# Peripherals.net
KiCad netlist of a schematic drawn in Altium Designer
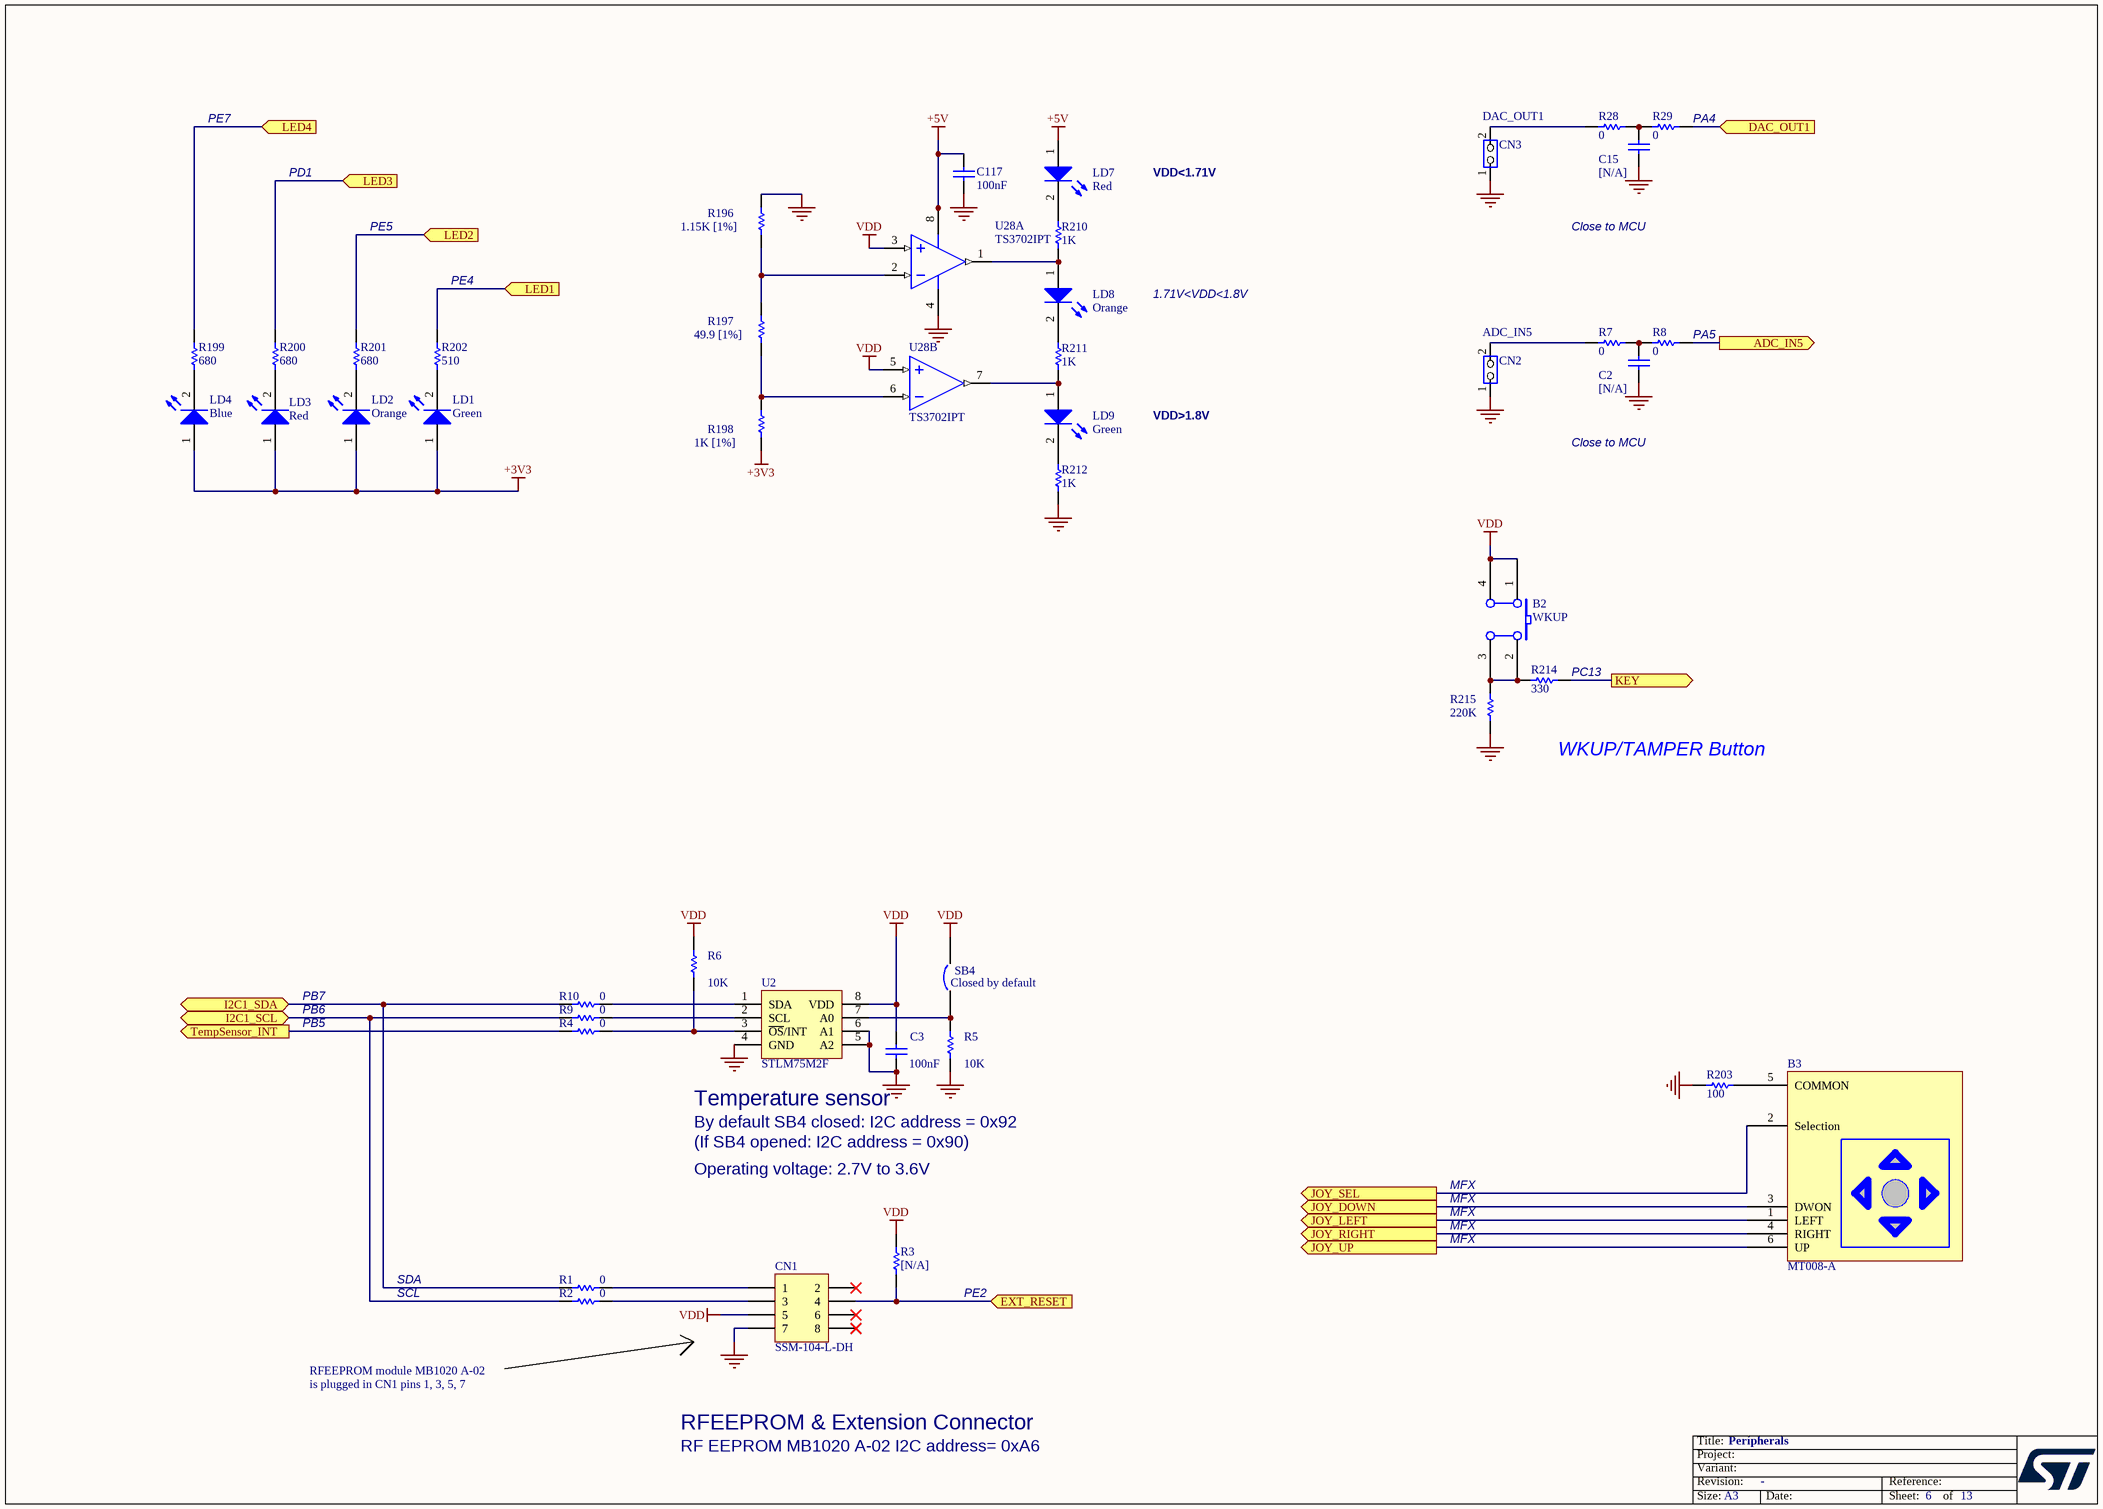
[diagram p0: Peripherals.SchDoc]

(export (version "E")
  (design (tool "Eeschema 10.0.6"))
  (components
    (comp (ref "B2")
      (value "WKUP")
      (footprint "PB10")
      (description "SE PUSHBUTTON")
      (libsource (lib "Documents") (part "SW PUSHBUTTON"))
    )
    (comp (ref "B3")
      (value "MT008-A")
      (footprint "MT-008A")
      (description "Joystick")
      (libsource (lib "MB513") (part "MT-008A"))
    )
    (comp (ref "C2")
      (value "[N/A]")
      (footprint "0603C")
      (description "Capacitor")
      (fields (field (name "PUBLISHER") "Altium Limited"))
      (libsource (lib "Miscellaneous Devices") (part "cap"))
    )
    (comp (ref "C3")
      (value "100nF")
      (footprint "0402C")
      (description "Capacitor")
      (fields (field (name "PUBLISHER") "Altium Limited"))
      (libsource (lib "Miscellaneous Devices") (part "cap"))
    )
    (comp (ref "C15")
      (value "[N/A]")
      (footprint "0603C")
      (description "Capacitor")
      (fields (field (name "PUBLISHER") "Altium Limited"))
      (libsource (lib "Miscellaneous Devices") (part "cap"))
    )
    (comp (ref "C117")
      (value "100nF")
      (footprint "0402C")
      (description "Capacitor")
      (fields (field (name "PUBLISHER") "Altium Limited"))
      (libsource (lib "Miscellaneous Devices") (part "CAP"))
    )
    (comp (ref "CN1")
      (value "SSM-104-L-DH")
      (footprint "SSM-104-L-DH")
      (description "Header, 5-Pin, Dual row")
      (fields (field (name "PUBLISHER") "Altium Limited"))
      (libsource (lib "mb1045") (part "SSM-104-L-DH"))
    )
    (comp (ref "CN2")
      (value "Header 2X1")
      (footprint "SIP2")
      (fields (field (name "SILKSCREEN") "ADC_IN5"))
      (libsource (lib "*") (part "JP2"))
    )
    (comp (ref "CN3")
      (value "Header 2X1")
      (footprint "SIP2")
      (fields (field (name "SILKSCREEN") "DAC_OUT1"))
      (libsource (lib "*") (part "JP2"))
    )
    (comp (ref "LD1")
      (value "Green")
      (footprint "0603D")
      (description "Typical RED, GREEN, YELLOW, AMBER GaAs LED")
      (fields (field (name "PUBLISHER") "Altium Limited"))
      (libsource (lib "Miscellaneous Devices") (part "LED2"))
    )
    (comp (ref "LD2")
      (value "Orange")
      (footprint "0603D")
      (description "Typical RED, GREEN, YELLOW, AMBER GaAs LED")
      (fields (field (name "PUBLISHER") "Altium Limited"))
      (libsource (lib "Miscellaneous Devices") (part "LED2"))
    )
    (comp (ref "LD3")
      (value "Red")
      (footprint "0603D")
      (description "Typical RED, GREEN, YELLOW, AMBER GaAs LED")
      (fields (field (name "PUBLISHER") "Altium Limited"))
      (libsource (lib "Miscellaneous Devices") (part "LED2"))
    )
    (comp (ref "LD4")
      (value "Blue")
      (footprint "0603D")
      (description "Typical RED, GREEN, YELLOW, AMBER GaAs LED")
      (fields (field (name "PUBLISHER") "Altium Limited"))
      (libsource (lib "Miscellaneous Devices") (part "LED2"))
    )
    (comp (ref "LD7")
      (value "Red")
      (footprint "0603D")
      (description "Typical RED, GREEN, YELLOW, AMBER GaAs LED")
      (fields (field (name "PUBLISHER") "Altium Limited"))
      (libsource (lib "Miscellaneous Devices") (part "LED2"))
    )
    (comp (ref "LD8")
      (value "Orange")
      (footprint "0603D")
      (description "Typical RED, GREEN, YELLOW, AMBER GaAs LED")
      (fields (field (name "PUBLISHER") "Altium Limited"))
      (libsource (lib "Miscellaneous Devices") (part "LED2"))
    )
    (comp (ref "LD9")
      (value "Green")
      (footprint "0603D")
      (description "Typical RED, GREEN, YELLOW, AMBER GaAs LED")
      (fields (field (name "PUBLISHER") "Altium Limited"))
      (libsource (lib "Miscellaneous Devices") (part "LED2"))
    )
    (comp (ref "R1")
      (value "0")
      (footprint "0603R")
      (description "Resistor")
      (fields (field (name "PUBLISHER") "Altium Limited"))
      (libsource (lib "Miscellaneous Devices") (part "Res1"))
    )
    (comp (ref "R2")
      (value "0")
      (footprint "0603R")
      (description "Resistor")
      (fields (field (name "PUBLISHER") "Altium Limited"))
      (libsource (lib "Miscellaneous Devices") (part "Res1"))
    )
    (comp (ref "R3")
      (value "[N/A]")
      (footprint "0603R")
      (description "Resistor")
      (fields (field (name "PUBLISHER") "Altium Limited"))
      (libsource (lib "Miscellaneous Devices") (part "Res1"))
    )
    (comp (ref "R4")
      (value "0")
      (footprint "0603R")
      (description "Resistor")
      (fields (field (name "PUBLISHER") "Altium Limited"))
      (libsource (lib "Miscellaneous Devices") (part "Res1"))
    )
    (comp (ref "R5")
      (value "10K")
      (footprint "0402R")
      (description "Resistor")
      (fields (field (name "PUBLISHER") "Altium Limited"))
      (libsource (lib "Miscellaneous Devices") (part "res1"))
    )
    (comp (ref "R6")
      (value "10K")
      (footprint "0402R")
      (description "Resistor")
      (fields (field (name "PUBLISHER") "Altium Limited"))
      (libsource (lib "Miscellaneous Devices") (part "res1"))
    )
    (comp (ref "R7")
      (value "0")
      (footprint "0603R")
      (description "Resistor")
      (fields (field (name "PUBLISHER") "Altium Limited"))
      (libsource (lib "Miscellaneous Devices") (part "Res1"))
    )
    (comp (ref "R8")
      (value "0")
      (footprint "0603R")
      (description "Resistor")
      (fields (field (name "PUBLISHER") "Altium Limited"))
      (libsource (lib "Miscellaneous Devices") (part "Res1"))
    )
    (comp (ref "R9")
      (value "0")
      (footprint "0603R")
      (description "Resistor")
      (fields (field (name "PUBLISHER") "Altium Limited"))
      (libsource (lib "Miscellaneous Devices") (part "Res1"))
    )
    (comp (ref "R10")
      (value "0")
      (footprint "0603R")
      (description "Resistor")
      (fields (field (name "PUBLISHER") "Altium Limited"))
      (libsource (lib "Miscellaneous Devices") (part "Res1"))
    )
    (comp (ref "R28")
      (value "0")
      (footprint "0603R")
      (description "Resistor")
      (fields (field (name "PUBLISHER") "Altium Limited"))
      (libsource (lib "Miscellaneous Devices") (part "Res1"))
    )
    (comp (ref "R29")
      (value "0")
      (footprint "0603R")
      (description "Resistor")
      (fields (field (name "PUBLISHER") "Altium Limited"))
      (libsource (lib "Miscellaneous Devices") (part "Res1"))
    )
    (comp (ref "R196")
      (value "1.15K [1%]")
      (footprint "0603R")
      (description "Resistor")
      (fields (field (name "PUBLISHER") "Altium Limited"))
      (libsource (lib "Miscellaneous Devices") (part "Res1"))
    )
    (comp (ref "R197")
      (value "49.9 [1%]")
      (footprint "0603R")
      (description "Resistor")
      (fields (field (name "PUBLISHER") "Altium Limited"))
      (libsource (lib "Miscellaneous Devices") (part "Res1"))
    )
    (comp (ref "R198")
      (value "1K [1%]")
      (footprint "0603R")
      (description "Resistor")
      (fields (field (name "PUBLISHER") "Altium Limited"))
      (libsource (lib "Miscellaneous Devices") (part "Res1"))
    )
    (comp (ref "R199")
      (value "680")
      (footprint "0402R")
      (description "Resistor")
      (fields (field (name "PUBLISHER") "Altium Limited"))
      (libsource (lib "Miscellaneous Devices") (part "Res1"))
    )
    (comp (ref "R200")
      (value "680")
      (footprint "0402R")
      (description "Resistor")
      (fields (field (name "PUBLISHER") "Altium Limited"))
      (libsource (lib "Miscellaneous Devices") (part "Res1"))
    )
    (comp (ref "R201")
      (value "680")
      (footprint "0402R")
      (description "Resistor")
      (fields (field (name "PUBLISHER") "Altium Limited"))
      (libsource (lib "Miscellaneous Devices") (part "Res1"))
    )
    (comp (ref "R202")
      (value "510")
      (footprint "0402R")
      (description "Resistor")
      (fields (field (name "PUBLISHER") "Altium Limited"))
      (libsource (lib "Miscellaneous Devices") (part "Res1"))
    )
    (comp (ref "R203")
      (value "100")
      (footprint "0402R")
      (description "Resistor")
      (fields (field (name "PUBLISHER") "Altium Limited"))
      (libsource (lib "Miscellaneous Devices") (part "Res1"))
    )
    (comp (ref "R210")
      (value "1K")
      (footprint "0402R")
      (description "Resistor")
      (fields (field (name "PUBLISHER") "Altium Limited"))
      (libsource (lib "Miscellaneous Devices") (part "Res1"))
    )
    (comp (ref "R211")
      (value "1K")
      (footprint "0402R")
      (description "Resistor")
      (fields (field (name "PUBLISHER") "Altium Limited"))
      (libsource (lib "Miscellaneous Devices") (part "Res1"))
    )
    (comp (ref "R212")
      (value "1K")
      (footprint "0402R")
      (description "Resistor")
      (fields (field (name "PUBLISHER") "Altium Limited"))
      (libsource (lib "Miscellaneous Devices") (part "Res1"))
    )
    (comp (ref "R214")
      (value "330")
      (footprint "0603R")
      (description "Resistor")
      (fields (field (name "PUBLISHER") "Altium Limited"))
      (libsource (lib "Miscellaneous Devices") (part "Res1"))
    )
    (comp (ref "R215")
      (value "220K")
      (footprint "0402R")
      (description "Resistor")
      (fields (field (name "PUBLISHER") "Altium Limited"))
      (libsource (lib "Miscellaneous Devices") (part "res1"))
    )
    (comp (ref "SB4")
      (value "Closed by default")
      (footprint "SB_0603")
      (description "Circuit Breaker")
      (fields (field (name "PUBLISHER") "Altium Limited"))
      (libsource (lib "Miscellaneous Devices") (part "Circuit Breaker"))
    )
    (comp (ref "U2")
      (value "STLM75M2F")
      (footprint "SOIC8_1R27_4R9X6")
      (libsource (lib "MB525") (part "STLM75DW2F"))
    )
    (comp (ref "U28")
      (value "TS3702IPT")
      (footprint "TSSOP8_0R65_3X6R4")
      (libsource (lib "MB819") (part "LM393PT"))
    )
  )
  (nets
    (net (code "1") (name "+3V3") (class "Default")
      (node (ref "LD1") (pin "1") (pinfunction "A_1") (pintype "passive"))
      (node (ref "LD2") (pin "1") (pinfunction "A_1") (pintype "passive"))
      (node (ref "LD3") (pin "1") (pinfunction "A_1") (pintype "passive"))
      (node (ref "LD4") (pin "1") (pinfunction "A_1") (pintype "passive"))
      (node (ref "R198") (pin "1") (pinfunction "1_1") (pintype "passive"))
    )
    (net (code "2") (name "+5V") (class "Default")
      (node (ref "C117") (pin "2") (pinfunction "2_2") (pintype "passive"))
      (node (ref "LD7") (pin "1") (pinfunction "A_1") (pintype "passive"))
      (node (ref "U28") (pin "8") (pinfunction "V+_8") (pintype "power_in"))
    )
    (net (code "3") (name "/ADC_IN5") (class "Default")
      (node (ref "R8") (pin "2") (pinfunction "2_2") (pintype "passive"))
    )
    (net (code "4") (name "/DAC_OUT1") (class "Default")
      (node (ref "R29") (pin "2") (pinfunction "2_2") (pintype "passive"))
    )
    (net (code "5") (name "/EXT_RESET") (class "Default")
      (node (ref "CN1") (pin "4") (pinfunction "4_4") (pintype "passive"))
      (node (ref "R3") (pin "1") (pinfunction "1_1") (pintype "passive"))
    )
    (net (code "6") (name "/I2C1_SCL") (class "Default")
      (node (ref "R2") (pin "1") (pinfunction "1_1") (pintype "passive"))
      (node (ref "R9") (pin "1") (pinfunction "1_1") (pintype "passive"))
    )
    (net (code "7") (name "/I2C1_SDA") (class "Default")
      (node (ref "R1") (pin "1") (pinfunction "1_1") (pintype "passive"))
      (node (ref "R10") (pin "1") (pinfunction "1_1") (pintype "passive"))
    )
    (net (code "8") (name "/JOY_DOWN") (class "Default")
      (node (ref "B3") (pin "3") (pinfunction "DWON_3") (pintype "passive"))
    )
    (net (code "9") (name "/JOY_LEFT") (class "Default")
      (node (ref "B3") (pin "1") (pinfunction "LEFT_1") (pintype "passive"))
    )
    (net (code "10") (name "/JOY_RIGHT") (class "Default")
      (node (ref "B3") (pin "4") (pinfunction "RIGHT_4") (pintype "passive"))
    )
    (net (code "11") (name "/JOY_SEL") (class "Default")
      (node (ref "B3") (pin "2") (pinfunction "Selection_2") (pintype "passive"))
    )
    (net (code "12") (name "/JOY_UP") (class "Default")
      (node (ref "B3") (pin "6") (pinfunction "UP_6") (pintype "passive"))
    )
    (net (code "13") (name "/KEY") (class "Default")
      (node (ref "R214") (pin "2") (pinfunction "2_2") (pintype "passive"))
    )
    (net (code "14") (name "/LED1") (class "Default")
      (node (ref "R202") (pin "1") (pinfunction "1_1") (pintype "passive"))
    )
    (net (code "15") (name "/LED2") (class "Default")
      (node (ref "R201") (pin "1") (pinfunction "1_1") (pintype "passive"))
    )
    (net (code "16") (name "/LED3") (class "Default")
      (node (ref "R200") (pin "1") (pinfunction "1_1") (pintype "passive"))
    )
    (net (code "17") (name "/LED4") (class "Default")
      (node (ref "R199") (pin "1") (pinfunction "1_1") (pintype "passive"))
    )
    (net (code "18") (name "/TempSensor_INT") (class "Default")
      (node (ref "R4") (pin "2") (pinfunction "2_2") (pintype "passive"))
    )
    (net (code "19") (name "GND") (class "Default")
      (node (ref "C117") (pin "1") (pinfunction "1_1") (pintype "passive"))
      (node (ref "C15") (pin "1") (pinfunction "1_1") (pintype "passive"))
      (node (ref "C2") (pin "1") (pinfunction "1_1") (pintype "passive"))
      (node (ref "C3") (pin "1") (pinfunction "1_1") (pintype "passive"))
      (node (ref "CN1") (pin "7") (pinfunction "7_7") (pintype "passive"))
      (node (ref "CN2") (pin "1") (pinfunction "COMMON_1") (pintype "passive"))
      (node (ref "CN3") (pin "1") (pinfunction "COMMON_1") (pintype "passive"))
      (node (ref "R196") (pin "2") (pinfunction "2_2") (pintype "passive"))
      (node (ref "R203") (pin "1") (pinfunction "1_1") (pintype "passive"))
      (node (ref "R212") (pin "2") (pinfunction "2_2") (pintype "passive"))
      (node (ref "R215") (pin "2") (pinfunction "2_2") (pintype "passive"))
      (node (ref "R5") (pin "2") (pinfunction "2_2") (pintype "passive"))
      (node (ref "U2") (pin "4") (pinfunction "GND_4") (pintype "passive"))
      (node (ref "U2") (pin "5") (pinfunction "A2_5") (pintype "passive"))
      (node (ref "U2") (pin "6") (pinfunction "A1_6") (pintype "passive"))
      (node (ref "U28") (pin "4") (pinfunction "V-_4") (pintype "power_in"))
    )
    (net (code "20") (name "Net-(B2-B0)") (class "Default")
      (node (ref "B2") (pin "2") (pinfunction "B0_2") (pintype "passive"))
      (node (ref "B2") (pin "3") (pinfunction "B1_3") (pintype "passive"))
      (node (ref "R214") (pin "1") (pinfunction "1_1") (pintype "passive"))
      (node (ref "R215") (pin "1") (pinfunction "1_1") (pintype "passive"))
    )
    (net (code "21") (name "Net-(B3-COMMON)") (class "Default")
      (node (ref "B3") (pin "5") (pinfunction "COMMON_5") (pintype "passive"))
      (node (ref "R203") (pin "2") (pinfunction "2_2") (pintype "passive"))
    )
    (net (code "22") (name "Net-(C2-Pad2)") (class "Default")
      (node (ref "C2") (pin "2") (pinfunction "2_2") (pintype "passive"))
      (node (ref "R7") (pin "2") (pinfunction "2_2") (pintype "passive"))
      (node (ref "R8") (pin "1") (pinfunction "1_1") (pintype "passive"))
    )
    (net (code "23") (name "Net-(C15-Pad2)") (class "Default")
      (node (ref "C15") (pin "2") (pinfunction "2_2") (pintype "passive"))
      (node (ref "R28") (pin "2") (pinfunction "2_2") (pintype "passive"))
      (node (ref "R29") (pin "1") (pinfunction "1_1") (pintype "passive"))
    )
    (net (code "24") (name "Net-(CN1-Pad1)") (class "Default")
      (node (ref "CN1") (pin "1") (pinfunction "1_1") (pintype "passive"))
      (node (ref "R1") (pin "2") (pinfunction "2_2") (pintype "passive"))
    )
    (net (code "25") (name "Net-(CN1-Pad3)") (class "Default")
      (node (ref "CN1") (pin "3") (pinfunction "3_3") (pintype "passive"))
      (node (ref "R2") (pin "2") (pinfunction "2_2") (pintype "passive"))
    )
    (net (code "26") (name "Net-(CN2-NO)") (class "Default")
      (node (ref "CN2") (pin "2") (pinfunction "NO_2") (pintype "passive"))
      (node (ref "R7") (pin "1") (pinfunction "1_1") (pintype "passive"))
    )
    (net (code "27") (name "Net-(CN3-NO)") (class "Default")
      (node (ref "CN3") (pin "2") (pinfunction "NO_2") (pintype "passive"))
      (node (ref "R28") (pin "1") (pinfunction "1_1") (pintype "passive"))
    )
    (net (code "28") (name "Net-(LD1-K)") (class "Default")
      (node (ref "LD1") (pin "2") (pinfunction "K_2") (pintype "passive"))
      (node (ref "R202") (pin "2") (pinfunction "2_2") (pintype "passive"))
    )
    (net (code "29") (name "Net-(LD2-K)") (class "Default")
      (node (ref "LD2") (pin "2") (pinfunction "K_2") (pintype "passive"))
      (node (ref "R201") (pin "2") (pinfunction "2_2") (pintype "passive"))
    )
    (net (code "30") (name "Net-(LD3-K)") (class "Default")
      (node (ref "LD3") (pin "2") (pinfunction "K_2") (pintype "passive"))
      (node (ref "R200") (pin "2") (pinfunction "2_2") (pintype "passive"))
    )
    (net (code "31") (name "Net-(LD4-K)") (class "Default")
      (node (ref "LD4") (pin "2") (pinfunction "K_2") (pintype "passive"))
      (node (ref "R199") (pin "2") (pinfunction "2_2") (pintype "passive"))
    )
    (net (code "32") (name "Net-(LD7-K)") (class "Default")
      (node (ref "LD7") (pin "2") (pinfunction "K_2") (pintype "passive"))
      (node (ref "R210") (pin "1") (pinfunction "1_1") (pintype "passive"))
    )
    (net (code "33") (name "Net-(LD8-A)") (class "Default")
      (node (ref "LD8") (pin "1") (pinfunction "A_1") (pintype "passive"))
      (node (ref "R210") (pin "2") (pinfunction "2_2") (pintype "passive"))
      (node (ref "U28") (pin "1") (pinfunction "OUT_1") (pintype "output"))
    )
    (net (code "34") (name "Net-(LD8-K)") (class "Default")
      (node (ref "LD8") (pin "2") (pinfunction "K_2") (pintype "passive"))
      (node (ref "R211") (pin "1") (pinfunction "1_1") (pintype "passive"))
    )
    (net (code "35") (name "Net-(LD9-A)") (class "Default")
      (node (ref "LD9") (pin "1") (pinfunction "A_1") (pintype "passive"))
      (node (ref "R211") (pin "2") (pinfunction "2_2") (pintype "passive"))
      (node (ref "U28") (pin "7") (pinfunction "OUT_7") (pintype "output"))
    )
    (net (code "36") (name "Net-(LD9-K)") (class "Default")
      (node (ref "LD9") (pin "2") (pinfunction "K_2") (pintype "passive"))
      (node (ref "R212") (pin "1") (pinfunction "1_1") (pintype "passive"))
    )
    (net (code "37") (name "Net-(U2-A0)") (class "Default")
      (node (ref "R5") (pin "1") (pinfunction "1_1") (pintype "passive"))
      (node (ref "SB4") (pin "1") (pinfunction "1_1") (pintype "passive"))
      (node (ref "U2") (pin "7") (pinfunction "A0_7") (pintype "passive"))
    )
    (net (code "38") (name "Net-(U2-SCL)") (class "Default")
      (node (ref "R9") (pin "2") (pinfunction "2_2") (pintype "passive"))
      (node (ref "U2") (pin "2") (pinfunction "SCL_2") (pintype "passive"))
    )
    (net (code "39") (name "Net-(U2-SDA)") (class "Default")
      (node (ref "R10") (pin "2") (pinfunction "2_2") (pintype "passive"))
      (node (ref "U2") (pin "1") (pinfunction "SDA_1") (pintype "passive"))
    )
    (net (code "40") (name "Net-(U2-~{OS}{slash}INT)") (class "Default")
      (node (ref "R4") (pin "1") (pinfunction "1_1") (pintype "passive"))
      (node (ref "R6") (pin "2") (pinfunction "2_2") (pintype "passive"))
      (node (ref "U2") (pin "3") (pinfunction "~{OS}/INT_3") (pintype "passive"))
    )
    (net (code "41") (name "Net-(U28A-IN-)") (class "Default")
      (node (ref "R196") (pin "1") (pinfunction "1_1") (pintype "passive"))
      (node (ref "R197") (pin "2") (pinfunction "2_2") (pintype "passive"))
      (node (ref "U28") (pin "2") (pinfunction "IN-_2") (pintype "input"))
    )
    (net (code "42") (name "Net-(U28B-IN-)") (class "Default")
      (node (ref "R197") (pin "1") (pinfunction "1_1") (pintype "passive"))
      (node (ref "R198") (pin "2") (pinfunction "2_2") (pintype "passive"))
      (node (ref "U28") (pin "6") (pinfunction "IN-_6") (pintype "input"))
    )
    (net (code "43") (name "VDD") (class "Default")
      (node (ref "B2") (pin "1") (pinfunction "A0_1") (pintype "passive"))
      (node (ref "B2") (pin "4") (pinfunction "A1_4") (pintype "passive"))
      (node (ref "C3") (pin "2") (pinfunction "2_2") (pintype "passive"))
      (node (ref "CN1") (pin "5") (pinfunction "5_5") (pintype "passive"))
      (node (ref "R3") (pin "2") (pinfunction "2_2") (pintype "passive"))
      (node (ref "R6") (pin "1") (pinfunction "1_1") (pintype "passive"))
      (node (ref "SB4") (pin "2") (pinfunction "2_2") (pintype "passive"))
      (node (ref "U2") (pin "8") (pinfunction "VDD_8") (pintype "passive"))
      (node (ref "U28") (pin "3") (pinfunction "IN+_3") (pintype "input"))
      (node (ref "U28") (pin "5") (pinfunction "IN+_5") (pintype "input"))
    )
    (net (code "44") (name "unconnected-(CN1-Pad2)") (class "Default")
      (node (ref "CN1") (pin "2") (pinfunction "2_2") (pintype "passive+no_connect"))
    )
    (net (code "45") (name "unconnected-(CN1-Pad6)") (class "Default")
      (node (ref "CN1") (pin "6") (pinfunction "6_6") (pintype "passive+no_connect"))
    )
    (net (code "46") (name "unconnected-(CN1-Pad8)") (class "Default")
      (node (ref "CN1") (pin "8") (pinfunction "8_8") (pintype "passive+no_connect"))
    )
  )
)
